# Logic_Inverter.net
KiCad netlist of a schematic drawn in Altium Designer
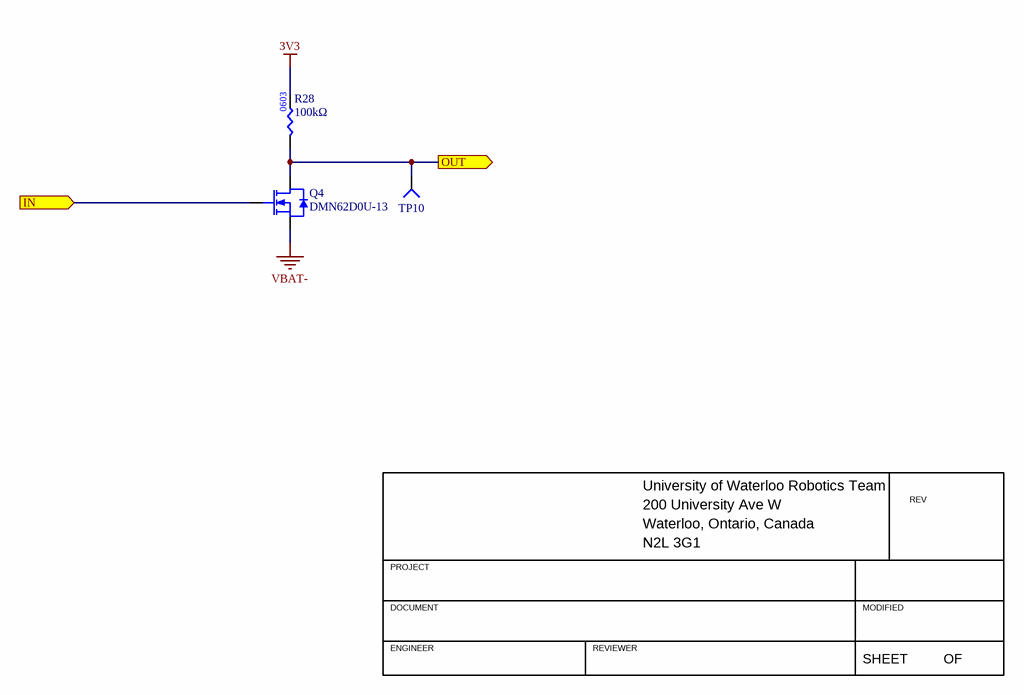
[diagram p0: Logic_Inverter.SchDoc]

(export (version "E")
  (design (tool "Eeschema 10.0.6"))
  (components
    (comp (ref "Q4")
      (value "NMOS_60V_380mA")
      (footprint "NMOS_SSOT-3")
      (description "MOSFET N-CH 60V 380MA SOT23")
      (fields (field (name "MANUFACTURER PART NUMBER 1") "DMN62D0U-13"))
      (libsource (lib "Personal_Schematic_Library_2022") (part "NMOS_60V_380mA"))
    )
    (comp (ref "R28")
      (value "100kΩ")
      (footprint "RES0603")
      (description "RES 100K OHM 1% 1/10W 0603")
      (fields (field (name "Comment") "RES_100kΩ_0603_1%"))
      (libsource (lib "Personal_Schematic_Library_2022") (part "RES_100kΩ_0603_1%"))
    )
    (comp (ref "TP10")
      (value "TESTPOINT_1MM_CIRCLE")
      (footprint "TESTPOINT_CIRCLE_1MM")
      (description "TESTPOINT 1MM CIRCLE")
      (libsource (lib "Personal_Schematic_Library_2022") (part "TESTPOINT_1MM_CIRCLE"))
    )
  )
  (nets
    (net (code "1") (name "/IN") (class "Default")
      (node (ref "Q4") (pin "1") (pinfunction "GATE_1") (pintype "passive"))
    )
    (net (code "2") (name "/OUT") (class "Default")
      (node (ref "Q4") (pin "3") (pinfunction "DRAIN_3") (pintype "passive"))
      (node (ref "R28") (pin "1") (pinfunction "1_1") (pintype "passive"))
      (node (ref "TP10") (pin "1") (pinfunction "=value_1") (pintype "passive"))
    )
    (net (code "3") (name "3V3") (class "Default")
      (node (ref "R28") (pin "2") (pinfunction "2_2") (pintype "passive"))
    )
    (net (code "4") (name "VBAT-") (class "Default")
      (node (ref "Q4") (pin "2") (pinfunction "SOURCE_2") (pintype "passive"))
    )
  )
)
